# 555_timer.net
KiCad netlist of a schematic drawn in Altium Designer
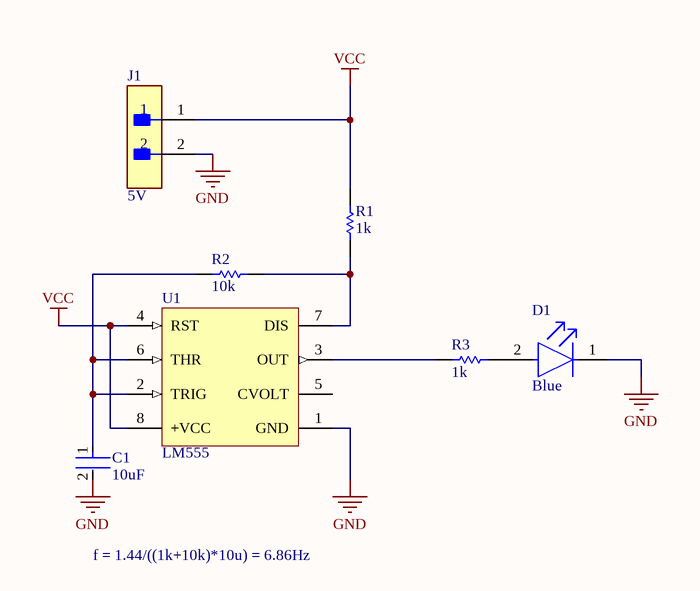
[diagram p0: 555_timer.SchDoc]

(export (version "E")
  (design (tool "Eeschema 10.0.6"))
  (components
    (comp (ref "C1")
      (value "10uF")
      (footprint "FP-C0805C-DN-IPC_A")
      (description "贴片电容（MLCC） 10μF ±10% 16V X5R 0805")
      (fields
        (field (name "MANUFACTURER") "Murata")
        (field (name "MANUFACTURER PART NUMBER") "GRM21BR61C106KE15L")
      )
      (libsource (lib "WEST_Schematic_Library") (part "GRM21BR61C106KE15L"))
    )
    (comp (ref "D1")
      (value "Blue")
      (footprint "FP-C0805C-DN-IPC_A")
      (description "LED BLUE CLEAR 0805 SMD")
      (fields
        (field (name "MANUFACTURER") "Vishay Lite-On")
        (field (name "MANUFACTURER PART NUMBER") "LTST-C170TBKT")
      )
      (libsource (lib "WEST_Schematic_Library") (part "LTST-C170TBKT"))
    )
    (comp (ref "J1")
      (value "5V")
      (footprint "FP-B2B-EH-A_LF_SN-MFG")
      (description "CONN HEADER EH TOP 2POS 2.5MM")
      (fields
        (field (name "MANUFACTURER") "JST")
        (field (name "MANUFACTURER PART NUMBER") "B2B-EH-A(LF)(SN)")
      )
      (libsource (lib "WEST_Schematic_Library") (part "B2B-EH-A(LF)(SN)"))
    )
    (comp (ref "R1")
      (value "1k")
      (footprint "FP-C0805C-DN-IPC_A")
      (description "Res Thick Film 0805 1K Ohm 1% 1/8W ±100ppm/°C Molded SMD Paper T/R")
      (fields
        (field (name "MANUFACTURER") "Vishay Dale")
        (field (name "MANUFACTURER PART NUMBER") "CRCW08051K00FKEA")
      )
      (libsource (lib "WEST_Schematic_Library") (part "CRCW08051K00FKEA"))
    )
    (comp (ref "R2")
      (value "10k")
      (footprint "FP-C0805C-DN-IPC_A")
      (description "Res Thick Film 0805 10K Ohm 1% 1/8W ±100ppm/°C Molded SMD Paper T/R")
      (fields
        (field (name "MANUFACTURER") "Vishay")
        (field (name "MANUFACTURER PART NUMBER") "CRCW080510K0FKEA")
      )
      (libsource (lib "WEST_Schematic_Library") (part "CRCW080510K0FKEA"))
    )
    (comp (ref "R3")
      (value "1k")
      (footprint "FP-C0805C-DN-IPC_A")
      (description "Res Thick Film 0805 1K Ohm 1% 1/8W ±100ppm/°C Molded SMD Paper T/R")
      (fields
        (field (name "MANUFACTURER") "Vishay Dale")
        (field (name "MANUFACTURER PART NUMBER") "CRCW08051K00FKEA")
      )
      (libsource (lib "WEST_Schematic_Library") (part "CRCW08051K00FKEA"))
    )
    (comp (ref "U1")
      (value "LM555")
      (footprint "N08E")
      (description "LM555 Series 16 V 7.5 mA Monolithic General Purpose Single Timer - DIP-8")
      (fields
        (field (name "MANUFACTURER") "TI National Semiconductor")
        (field (name "MANUFACTURER PART NUMBER") "LM555CN")
      )
      (libsource (lib "WEST_Schematic_Library") (part "LM555CN"))
    )
  )
  (nets
    (net (code "1") (name "GND") (class "Default")
      (node (ref "C1") (pin "2") (pinfunction "2_2") (pintype "passive"))
      (node (ref "D1") (pin "1") (pinfunction "C_1") (pintype "passive"))
      (node (ref "J1") (pin "2") (pinfunction "2_2") (pintype "passive"))
      (node (ref "U1") (pin "1") (pinfunction "GND_1") (pintype "power_in"))
    )
    (net (code "2") (name "Net-(D1-A)") (class "Default")
      (node (ref "D1") (pin "2") (pinfunction "A_2") (pintype "passive"))
      (node (ref "R3") (pin "2") (pinfunction "2_2") (pintype "passive"))
    )
    (net (code "3") (name "Net-(U1-DIS)") (class "Default")
      (node (ref "R1") (pin "1") (pinfunction "1_1") (pintype "passive"))
      (node (ref "R2") (pin "2") (pinfunction "2_2") (pintype "passive"))
      (node (ref "U1") (pin "7") (pinfunction "DIS_7") (pintype "open_collector"))
    )
    (net (code "4") (name "Net-(U1-OUT)") (class "Default")
      (node (ref "R3") (pin "1") (pinfunction "1_1") (pintype "passive"))
      (node (ref "U1") (pin "3") (pinfunction "OUT_3") (pintype "output"))
    )
    (net (code "5") (name "Net-(U1-THR)") (class "Default")
      (node (ref "C1") (pin "1") (pinfunction "1_1") (pintype "passive"))
      (node (ref "R2") (pin "1") (pinfunction "1_1") (pintype "passive"))
      (node (ref "U1") (pin "2") (pinfunction "TRIG_2") (pintype "input"))
      (node (ref "U1") (pin "6") (pinfunction "THR_6") (pintype "input"))
    )
    (net (code "6") (name "VCC") (class "Default")
      (node (ref "J1") (pin "1") (pinfunction "1_1") (pintype "passive"))
      (node (ref "R1") (pin "2") (pinfunction "2_2") (pintype "passive"))
      (node (ref "U1") (pin "4") (pinfunction "RST_4") (pintype "input"))
      (node (ref "U1") (pin "8") (pinfunction "+VCC_8") (pintype "power_in"))
    )
    (net (code "7") (name "unconnected-(U1-CVOLT-Pad5)") (class "Default")
      (node (ref "U1") (pin "5") (pinfunction "CVOLT_5") (pintype "passive"))
    )
  )
)
